# SCH_Macro_Pod_Lite_Easy_EDA.net
KiCad netlist of a schematic drawn in EasyEDA
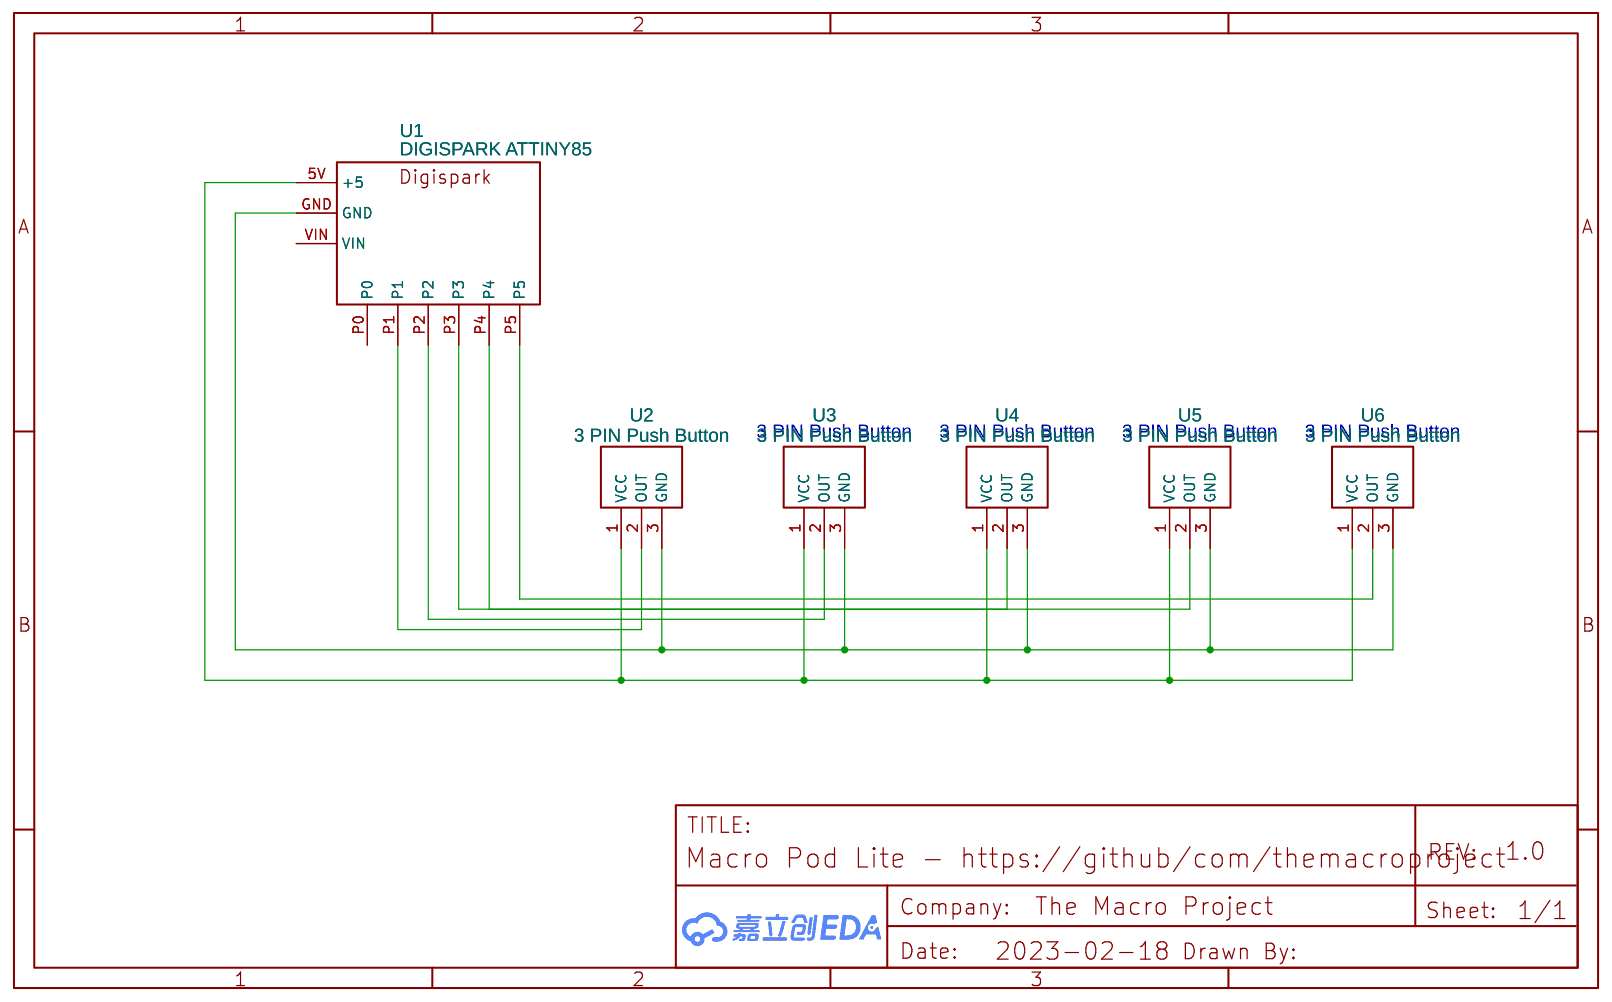
[diagram p0: schematic sheet]

(export (version "E")
  (design (tool "Eeschema 10.0.6"))
  (components
    (comp (ref "U1")
      (value "DIGISPARK ATTINY85")
      (fields (field (name "BOM_Manufacturer Part") "Digispark"))
      (libsource (lib "") (part "DIGISPARK ATTINI85"))
    )
    (comp (ref "U2") (value "3 PIN Push Button") (libsource (lib "") (part "3 PIN Push Button copy")))
    (comp (ref "U3") (value "3 PIN Push Button") (libsource (lib "") (part "3 PIN Push Button copy")))
    (comp (ref "U4") (value "3 PIN Push Button") (libsource (lib "") (part "3 PIN Push Button copy")))
    (comp (ref "U5") (value "3 PIN Push Button") (libsource (lib "") (part "3 PIN Push Button copy")))
    (comp (ref "U6") (value "3 PIN Push Button") (libsource (lib "") (part "3 PIN Push Button copy")))
  )
  (nets
    (net (code "1") (name "Net-(U1-+5)") (class "Default")
      (node (ref "U1") (pin "5V") (pinfunction "+5_5V") (pintype "unspecified"))
      (node (ref "U2") (pin "1") (pinfunction "VCC_1") (pintype "unspecified"))
      (node (ref "U3") (pin "1") (pinfunction "VCC_1") (pintype "unspecified"))
      (node (ref "U4") (pin "1") (pinfunction "VCC_1") (pintype "unspecified"))
      (node (ref "U5") (pin "1") (pinfunction "VCC_1") (pintype "unspecified"))
      (node (ref "U6") (pin "1") (pinfunction "VCC_1") (pintype "unspecified"))
    )
    (net (code "2") (name "Net-(U2-GND)") (class "Default")
      (node (ref "U1") (pin "GND") (pinfunction "GND_GND") (pintype "unspecified"))
      (node (ref "U2") (pin "3") (pinfunction "GND_3") (pintype "unspecified"))
      (node (ref "U3") (pin "3") (pinfunction "GND_3") (pintype "unspecified"))
      (node (ref "U4") (pin "3") (pinfunction "GND_3") (pintype "unspecified"))
      (node (ref "U5") (pin "3") (pinfunction "GND_3") (pintype "unspecified"))
      (node (ref "U6") (pin "3") (pinfunction "GND_3") (pintype "unspecified"))
    )
    (net (code "3") (name "Net-(U2-OUT)") (class "Default")
      (node (ref "U1") (pin "P1") (pinfunction "P1_P1") (pintype "unspecified"))
      (node (ref "U2") (pin "2") (pinfunction "OUT_2") (pintype "unspecified"))
    )
    (net (code "4") (name "Net-(U3-OUT)") (class "Default")
      (node (ref "U1") (pin "P2") (pinfunction "P2_P2") (pintype "unspecified"))
      (node (ref "U3") (pin "2") (pinfunction "OUT_2") (pintype "unspecified"))
    )
    (net (code "5") (name "Net-(U4-OUT)") (class "Default")
      (node (ref "U1") (pin "P3") (pinfunction "P3_P3") (pintype "unspecified"))
      (node (ref "U4") (pin "2") (pinfunction "OUT_2") (pintype "unspecified"))
    )
    (net (code "6") (name "Net-(U5-OUT)") (class "Default")
      (node (ref "U1") (pin "P4") (pinfunction "P4_P4") (pintype "unspecified"))
      (node (ref "U5") (pin "2") (pinfunction "OUT_2") (pintype "unspecified"))
    )
    (net (code "7") (name "Net-(U6-OUT)") (class "Default")
      (node (ref "U1") (pin "P5") (pinfunction "P5_P5") (pintype "unspecified"))
      (node (ref "U6") (pin "2") (pinfunction "OUT_2") (pintype "unspecified"))
    )
    (net (code "8") (name "unconnected-(U1-PadP0)") (class "Default")
      (node (ref "U1") (pin "P0") (pinfunction "P0_P0") (pintype "unspecified"))
    )
    (net (code "9") (name "unconnected-(U1-PadVIN)") (class "Default")
      (node (ref "U1") (pin "VIN") (pinfunction "VIN_VIN") (pintype "unspecified"))
    )
  )
)
